# 20-pin_SOIC_TSSOP.net
KiCad netlist of a schematic drawn in EAGLE
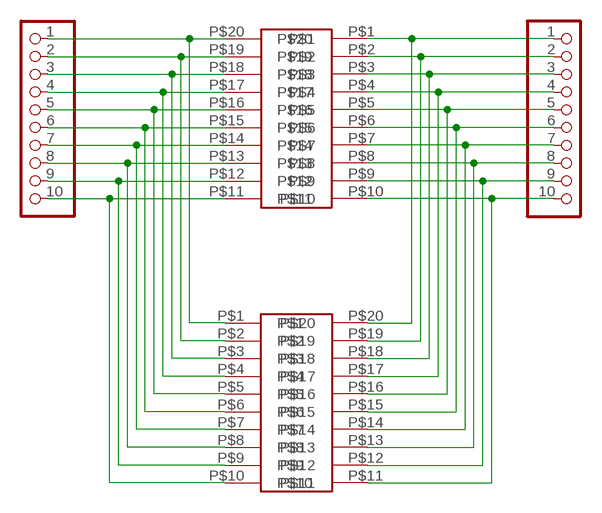
[diagram p0: schematic, sheet 1]

(export (version "E")
  (design (tool "Eeschema 10.0.6"))
  (components
    (comp (ref "U$1")
      (value "20-PINSOIC-NW")
      (footprint "eagle-import:SO20-NW")
      (libsource (lib "eagle-import") (part "20-PINSOIC-NW"))
    )
    (comp (ref "U$2")
      (value "20-PINTSSOP-NW")
      (footprint "eagle-import:TSSOP20-NW")
      (libsource (lib "eagle-import") (part "20-PINTSSOP-NW"))
    )
    (comp (ref "U$3")
      (value "PADS-10")
      (footprint "eagle-import:PADS-10")
      (libsource (lib "eagle-import") (part "PADS-10"))
    )
    (comp (ref "U$4")
      (value "PADS-10")
      (footprint "eagle-import:PADS-10")
      (libsource (lib "eagle-import") (part "PADS-10"))
    )
  )
  (nets
    (net (code "1") (name "Net-(U$1-PadP$1)") (class "Default")
      (node (ref "U$1") (pin "P$1") (pinfunction "P$1_P$1") (pintype "bidirectional"))
      (node (ref "U$2") (pin "P$20") (pinfunction "P$20_P$20") (pintype "bidirectional"))
      (node (ref "U$3") (pin "1") (pinfunction "1_1") (pintype "passive"))
    )
    (net (code "2") (name "Net-(U$1-PadP$2)") (class "Default")
      (node (ref "U$1") (pin "P$2") (pinfunction "P$2_P$2") (pintype "bidirectional"))
      (node (ref "U$2") (pin "P$19") (pinfunction "P$19_P$19") (pintype "bidirectional"))
      (node (ref "U$3") (pin "2") (pinfunction "2_2") (pintype "passive"))
    )
    (net (code "3") (name "Net-(U$1-PadP$3)") (class "Default")
      (node (ref "U$1") (pin "P$3") (pinfunction "P$3_P$3") (pintype "bidirectional"))
      (node (ref "U$2") (pin "P$18") (pinfunction "P$18_P$18") (pintype "bidirectional"))
      (node (ref "U$3") (pin "3") (pinfunction "3_3") (pintype "passive"))
    )
    (net (code "4") (name "Net-(U$1-PadP$4)") (class "Default")
      (node (ref "U$1") (pin "P$4") (pinfunction "P$4_P$4") (pintype "bidirectional"))
      (node (ref "U$2") (pin "P$17") (pinfunction "P$17_P$17") (pintype "bidirectional"))
      (node (ref "U$3") (pin "4") (pinfunction "4_4") (pintype "passive"))
    )
    (net (code "5") (name "Net-(U$1-PadP$5)") (class "Default")
      (node (ref "U$1") (pin "P$5") (pinfunction "P$5_P$5") (pintype "bidirectional"))
      (node (ref "U$2") (pin "P$16") (pinfunction "P$16_P$16") (pintype "bidirectional"))
      (node (ref "U$3") (pin "5") (pinfunction "5_5") (pintype "passive"))
    )
    (net (code "6") (name "Net-(U$1-PadP$6)") (class "Default")
      (node (ref "U$1") (pin "P$6") (pinfunction "P$6_P$6") (pintype "bidirectional"))
      (node (ref "U$2") (pin "P$15") (pinfunction "P$15_P$15") (pintype "bidirectional"))
      (node (ref "U$3") (pin "6") (pinfunction "6_6") (pintype "passive"))
    )
    (net (code "7") (name "Net-(U$1-PadP$7)") (class "Default")
      (node (ref "U$1") (pin "P$7") (pinfunction "P$7_P$7") (pintype "bidirectional"))
      (node (ref "U$2") (pin "P$14") (pinfunction "P$14_P$14") (pintype "bidirectional"))
      (node (ref "U$3") (pin "7") (pinfunction "7_7") (pintype "passive"))
    )
    (net (code "8") (name "Net-(U$1-PadP$8)") (class "Default")
      (node (ref "U$1") (pin "P$8") (pinfunction "P$8_P$8") (pintype "bidirectional"))
      (node (ref "U$2") (pin "P$13") (pinfunction "P$13_P$13") (pintype "bidirectional"))
      (node (ref "U$3") (pin "8") (pinfunction "8_8") (pintype "passive"))
    )
    (net (code "9") (name "Net-(U$1-PadP$9)") (class "Default")
      (node (ref "U$1") (pin "P$9") (pinfunction "P$9_P$9") (pintype "bidirectional"))
      (node (ref "U$2") (pin "P$12") (pinfunction "P$12_P$12") (pintype "bidirectional"))
      (node (ref "U$3") (pin "9") (pinfunction "9_9") (pintype "passive"))
    )
    (net (code "10") (name "Net-(U$1-PadP$10)") (class "Default")
      (node (ref "U$1") (pin "P$10") (pinfunction "P$10_P$10") (pintype "bidirectional"))
      (node (ref "U$2") (pin "P$11") (pinfunction "P$11_P$11") (pintype "bidirectional"))
      (node (ref "U$3") (pin "10") (pinfunction "10_10") (pintype "passive"))
    )
    (net (code "11") (name "Net-(U$1-PadP$11)") (class "Default")
      (node (ref "U$1") (pin "P$11") (pinfunction "P$11_P$11") (pintype "bidirectional"))
      (node (ref "U$2") (pin "P$10") (pinfunction "P$10_P$10") (pintype "bidirectional"))
      (node (ref "U$4") (pin "10") (pinfunction "10_10") (pintype "passive"))
    )
    (net (code "12") (name "Net-(U$1-PadP$12)") (class "Default")
      (node (ref "U$1") (pin "P$12") (pinfunction "P$12_P$12") (pintype "bidirectional"))
      (node (ref "U$2") (pin "P$9") (pinfunction "P$9_P$9") (pintype "bidirectional"))
      (node (ref "U$4") (pin "9") (pinfunction "9_9") (pintype "passive"))
    )
    (net (code "13") (name "Net-(U$1-PadP$13)") (class "Default")
      (node (ref "U$1") (pin "P$13") (pinfunction "P$13_P$13") (pintype "bidirectional"))
      (node (ref "U$2") (pin "P$8") (pinfunction "P$8_P$8") (pintype "bidirectional"))
      (node (ref "U$4") (pin "8") (pinfunction "8_8") (pintype "passive"))
    )
    (net (code "14") (name "Net-(U$1-PadP$14)") (class "Default")
      (node (ref "U$1") (pin "P$14") (pinfunction "P$14_P$14") (pintype "bidirectional"))
      (node (ref "U$2") (pin "P$7") (pinfunction "P$7_P$7") (pintype "bidirectional"))
      (node (ref "U$4") (pin "7") (pinfunction "7_7") (pintype "passive"))
    )
    (net (code "15") (name "Net-(U$1-PadP$15)") (class "Default")
      (node (ref "U$1") (pin "P$15") (pinfunction "P$15_P$15") (pintype "bidirectional"))
      (node (ref "U$2") (pin "P$6") (pinfunction "P$6_P$6") (pintype "bidirectional"))
      (node (ref "U$4") (pin "6") (pinfunction "6_6") (pintype "passive"))
    )
    (net (code "16") (name "Net-(U$1-PadP$16)") (class "Default")
      (node (ref "U$1") (pin "P$16") (pinfunction "P$16_P$16") (pintype "bidirectional"))
      (node (ref "U$2") (pin "P$5") (pinfunction "P$5_P$5") (pintype "bidirectional"))
      (node (ref "U$4") (pin "5") (pinfunction "5_5") (pintype "passive"))
    )
    (net (code "17") (name "Net-(U$1-PadP$17)") (class "Default")
      (node (ref "U$1") (pin "P$17") (pinfunction "P$17_P$17") (pintype "bidirectional"))
      (node (ref "U$2") (pin "P$4") (pinfunction "P$4_P$4") (pintype "bidirectional"))
      (node (ref "U$4") (pin "4") (pinfunction "4_4") (pintype "passive"))
    )
    (net (code "18") (name "Net-(U$1-PadP$18)") (class "Default")
      (node (ref "U$1") (pin "P$18") (pinfunction "P$18_P$18") (pintype "bidirectional"))
      (node (ref "U$2") (pin "P$3") (pinfunction "P$3_P$3") (pintype "bidirectional"))
      (node (ref "U$4") (pin "3") (pinfunction "3_3") (pintype "passive"))
    )
    (net (code "19") (name "Net-(U$1-PadP$19)") (class "Default")
      (node (ref "U$1") (pin "P$19") (pinfunction "P$19_P$19") (pintype "bidirectional"))
      (node (ref "U$2") (pin "P$2") (pinfunction "P$2_P$2") (pintype "bidirectional"))
      (node (ref "U$4") (pin "2") (pinfunction "2_2") (pintype "passive"))
    )
    (net (code "20") (name "Net-(U$1-PadP$20)") (class "Default")
      (node (ref "U$1") (pin "P$20") (pinfunction "P$20_P$20") (pintype "bidirectional"))
      (node (ref "U$2") (pin "P$1") (pinfunction "P$1_P$1") (pintype "bidirectional"))
      (node (ref "U$4") (pin "1") (pinfunction "1_1") (pintype "passive"))
    )
  )
)
